# FullPrototypingBoard.net
KiCad netlist of a schematic drawn in EAGLE
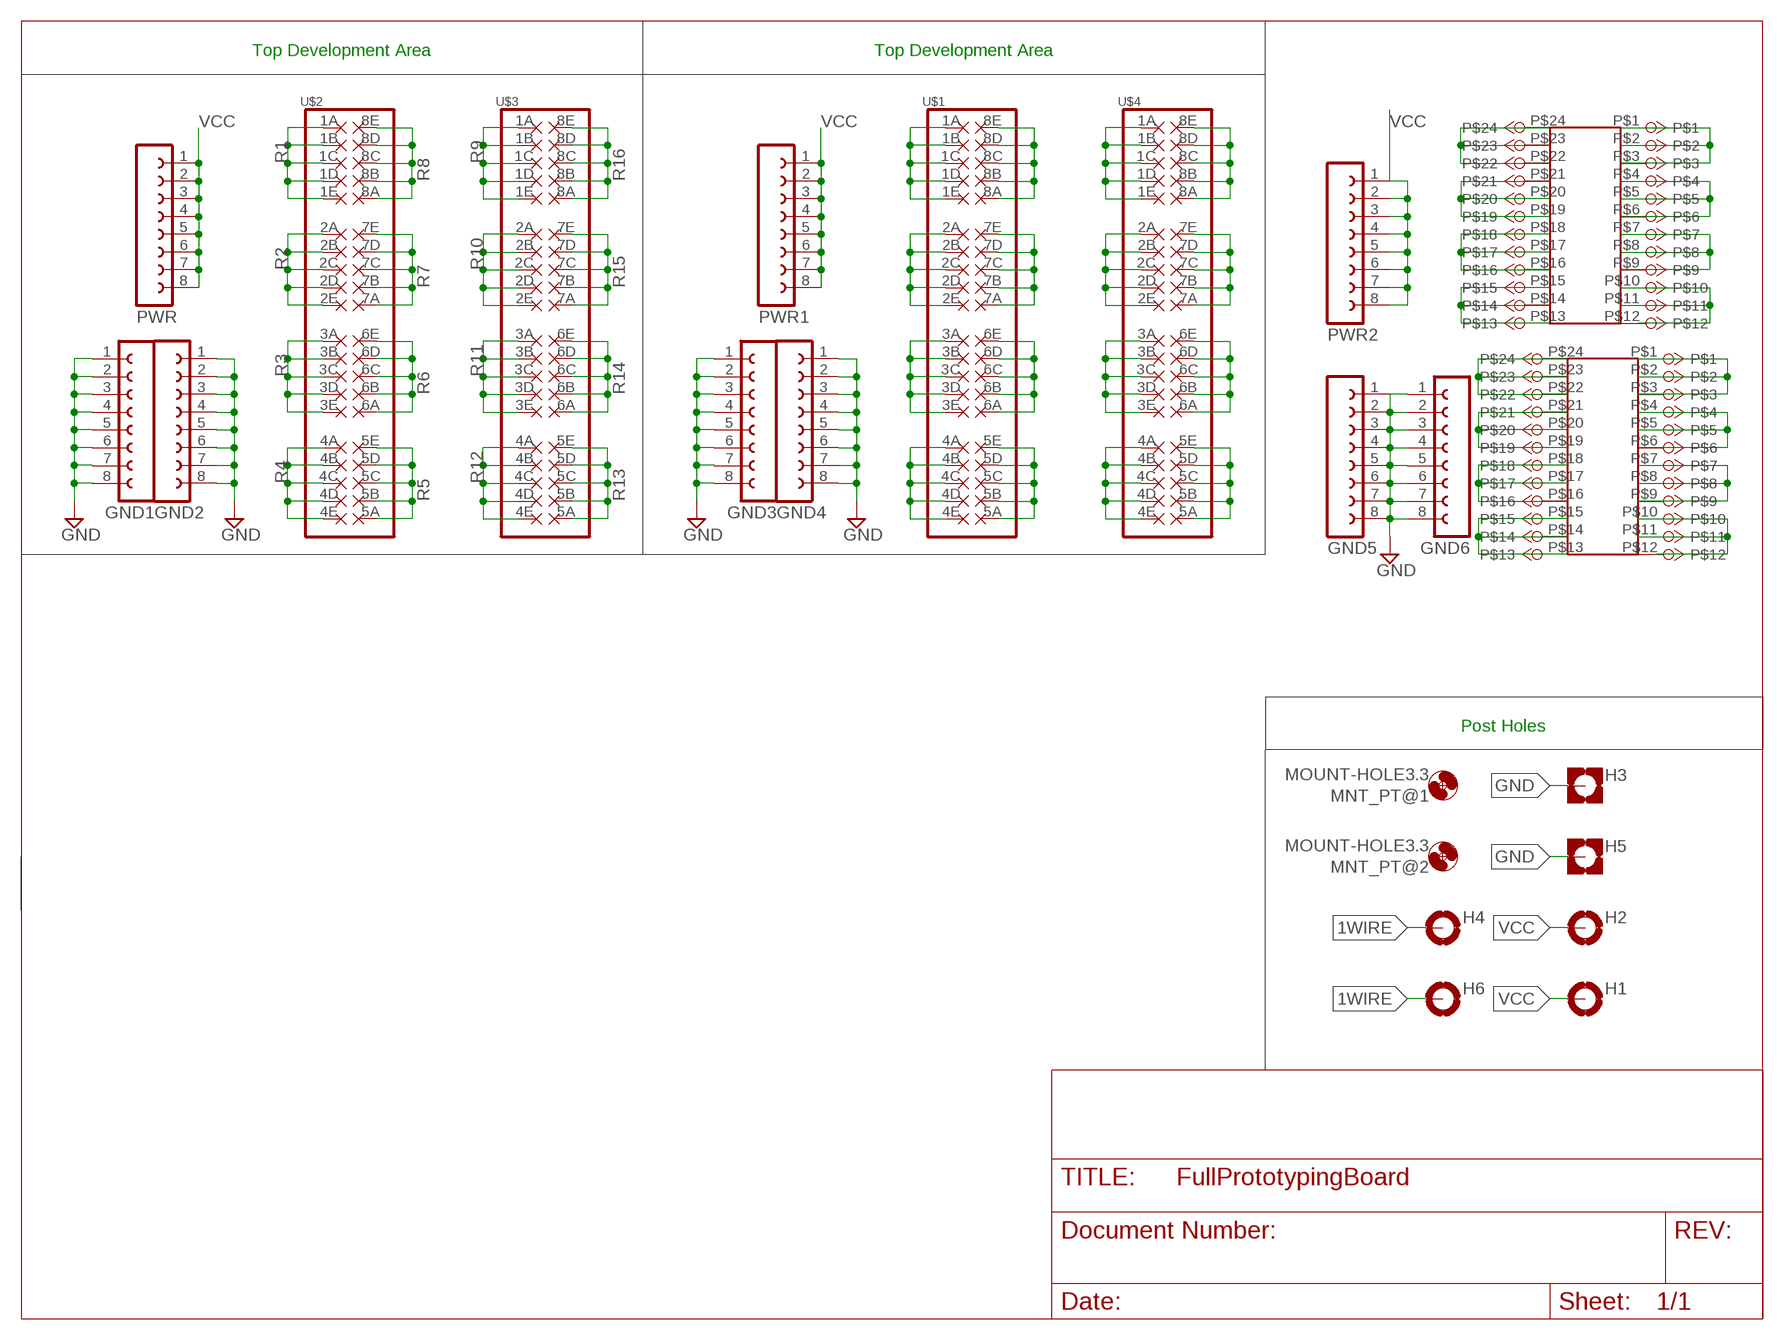
[diagram p0: schematic, sheet 1]

(export (version "E")
  (design (tool "Eeschema 10.0.6"))
  (components
    (comp (ref "GND1")
      (value "FE08-1-GND")
      (footprint "eagle-import:FE08-GND")
      (libsource (lib "eagle-import") (part "FE08-1-GND"))
    )
    (comp (ref "GND2")
      (value "FE08-1-GND")
      (footprint "eagle-import:FE08-GND")
      (libsource (lib "eagle-import") (part "FE08-1-GND"))
    )
    (comp (ref "GND3")
      (value "FE08-1-GND")
      (footprint "eagle-import:FE08-GND")
      (libsource (lib "eagle-import") (part "FE08-1-GND"))
    )
    (comp (ref "GND4")
      (value "FE08-1-GND")
      (footprint "eagle-import:FE08-GND")
      (libsource (lib "eagle-import") (part "FE08-1-GND"))
    )
    (comp (ref "GND5")
      (value "FE08-1-GND")
      (footprint "eagle-import:FE08-GND")
      (libsource (lib "eagle-import") (part "FE08-1-GND"))
    )
    (comp (ref "GND6")
      (value "FE08-1-GND")
      (footprint "eagle-import:FE08-GND")
      (libsource (lib "eagle-import") (part "FE08-1-GND"))
    )
    (comp (ref "H1")
      (value "MOUNT-PAD-ROUND3.3")
      (footprint "eagle-import:3,3-PAD")
      (libsource (lib "eagle-import") (part "MOUNT-PAD-ROUND3.3"))
    )
    (comp (ref "H2")
      (value "MOUNT-PAD-ROUND3.3")
      (footprint "eagle-import:3,3-PAD")
      (libsource (lib "eagle-import") (part "MOUNT-PAD-ROUND3.3"))
    )
    (comp (ref "H3")
      (value "MOUNT-PAD-SQUARE3.3")
      (footprint "eagle-import:3,3-PAD-SQUARE")
      (libsource (lib "eagle-import") (part "MOUNT-PAD-SQUARE3.3"))
    )
    (comp (ref "H4")
      (value "MOUNT-PAD-ROUND3.3")
      (footprint "eagle-import:3,3-PAD")
      (libsource (lib "eagle-import") (part "MOUNT-PAD-ROUND3.3"))
    )
    (comp (ref "H5")
      (value "MOUNT-PAD-SQUARE3.3")
      (footprint "eagle-import:3,3-PAD-SQUARE")
      (libsource (lib "eagle-import") (part "MOUNT-PAD-SQUARE3.3"))
    )
    (comp (ref "H6")
      (value "MOUNT-PAD-ROUND3.3")
      (footprint "eagle-import:3,3-PAD")
      (libsource (lib "eagle-import") (part "MOUNT-PAD-ROUND3.3"))
    )
    (comp (ref "MNT_PT@1")
      (value "MOUNT-HOLE3.3")
      (footprint "eagle-import:3,3")
      (libsource (lib "eagle-import") (part "MOUNT-HOLE3.3"))
    )
    (comp (ref "MNT_PT@2")
      (value "MOUNT-HOLE3.3")
      (footprint "eagle-import:3,3")
      (libsource (lib "eagle-import") (part "MOUNT-HOLE3.3"))
    )
    (comp (ref "PWR")
      (value "FE08-1")
      (footprint "eagle-import:FE08")
      (libsource (lib "eagle-import") (part "FE08-1"))
    )
    (comp (ref "PWR1")
      (value "FE08-1")
      (footprint "eagle-import:FE08")
      (libsource (lib "eagle-import") (part "FE08-1"))
    )
    (comp (ref "PWR2")
      (value "FE08-1")
      (footprint "eagle-import:FE08")
      (libsource (lib "eagle-import") (part "FE08-1"))
    )
    (comp (ref "U$1")
      (value "PROTO-5X8")
      (footprint "eagle-import:PROTO-5X08")
      (libsource (lib "eagle-import") (part "PROTO-5X8"))
    )
    (comp (ref "U$2")
      (value "PROTO-5X8")
      (footprint "eagle-import:PROTO-5X08")
      (libsource (lib "eagle-import") (part "PROTO-5X8"))
    )
    (comp (ref "U$3")
      (value "PROTO-5X8")
      (footprint "eagle-import:PROTO-5X08")
      (libsource (lib "eagle-import") (part "PROTO-5X8"))
    )
    (comp (ref "U$4")
      (value "PROTO-5X8")
      (footprint "eagle-import:PROTO-5X08")
      (libsource (lib "eagle-import") (part "PROTO-5X8"))
    )
    (comp (ref "U$5")
      (value "PROTO-3X8")
      (footprint "eagle-import:PROTO-3X08")
      (libsource (lib "eagle-import") (part "PROTO-3X8"))
    )
    (comp (ref "U$6")
      (value "PROTO-3X8")
      (footprint "eagle-import:PROTO-3X08")
      (libsource (lib "eagle-import") (part "PROTO-3X8"))
    )
  )
  (nets
    (net (code "1") (name "/R1") (class "Default")
      (node (ref "U$2") (pin "1A") (pinfunction "1A_1A") (pintype "passive"))
      (node (ref "U$2") (pin "1B") (pinfunction "1B_1B") (pintype "passive"))
      (node (ref "U$2") (pin "1C") (pinfunction "1C_1C") (pintype "passive"))
      (node (ref "U$2") (pin "1D") (pinfunction "1D_1D") (pintype "passive"))
      (node (ref "U$2") (pin "1E") (pinfunction "1E_1E") (pintype "passive"))
    )
    (net (code "2") (name "/R2") (class "Default")
      (node (ref "U$2") (pin "2A") (pinfunction "2A_2A") (pintype "passive"))
      (node (ref "U$2") (pin "2B") (pinfunction "2B_2B") (pintype "passive"))
      (node (ref "U$2") (pin "2C") (pinfunction "2C_2C") (pintype "passive"))
      (node (ref "U$2") (pin "2D") (pinfunction "2D_2D") (pintype "passive"))
      (node (ref "U$2") (pin "2E") (pinfunction "2E_2E") (pintype "passive"))
    )
    (net (code "3") (name "/R3") (class "Default")
      (node (ref "U$2") (pin "3A") (pinfunction "3A_3A") (pintype "passive"))
      (node (ref "U$2") (pin "3B") (pinfunction "3B_3B") (pintype "passive"))
      (node (ref "U$2") (pin "3C") (pinfunction "3C_3C") (pintype "passive"))
      (node (ref "U$2") (pin "3D") (pinfunction "3D_3D") (pintype "passive"))
      (node (ref "U$2") (pin "3E") (pinfunction "3E_3E") (pintype "passive"))
    )
    (net (code "4") (name "/R4") (class "Default")
      (node (ref "U$2") (pin "4A") (pinfunction "4A_4A") (pintype "passive"))
      (node (ref "U$2") (pin "4B") (pinfunction "4B_4B") (pintype "passive"))
      (node (ref "U$2") (pin "4C") (pinfunction "4C_4C") (pintype "passive"))
      (node (ref "U$2") (pin "4D") (pinfunction "4D_4D") (pintype "passive"))
      (node (ref "U$2") (pin "4E") (pinfunction "4E_4E") (pintype "passive"))
    )
    (net (code "5") (name "/R5") (class "Default")
      (node (ref "U$2") (pin "5A") (pinfunction "5A_5A") (pintype "passive"))
      (node (ref "U$2") (pin "5B") (pinfunction "5B_5B") (pintype "passive"))
      (node (ref "U$2") (pin "5C") (pinfunction "5C_5C") (pintype "passive"))
      (node (ref "U$2") (pin "5D") (pinfunction "5D_5D") (pintype "passive"))
      (node (ref "U$2") (pin "5E") (pinfunction "5E_5E") (pintype "passive"))
    )
    (net (code "6") (name "/R6") (class "Default")
      (node (ref "U$2") (pin "6A") (pinfunction "6A_6A") (pintype "passive"))
      (node (ref "U$2") (pin "6B") (pinfunction "6B_6B") (pintype "passive"))
      (node (ref "U$2") (pin "6C") (pinfunction "6C_6C") (pintype "passive"))
      (node (ref "U$2") (pin "6D") (pinfunction "6D_6D") (pintype "passive"))
      (node (ref "U$2") (pin "6E") (pinfunction "6E_6E") (pintype "passive"))
    )
    (net (code "7") (name "/R7") (class "Default")
      (node (ref "U$2") (pin "7A") (pinfunction "7A_7A") (pintype "passive"))
      (node (ref "U$2") (pin "7B") (pinfunction "7B_7B") (pintype "passive"))
      (node (ref "U$2") (pin "7C") (pinfunction "7C_7C") (pintype "passive"))
      (node (ref "U$2") (pin "7D") (pinfunction "7D_7D") (pintype "passive"))
      (node (ref "U$2") (pin "7E") (pinfunction "7E_7E") (pintype "passive"))
    )
    (net (code "8") (name "/R8") (class "Default")
      (node (ref "U$2") (pin "8A") (pinfunction "8A_8A") (pintype "passive"))
      (node (ref "U$2") (pin "8B") (pinfunction "8B_8B") (pintype "passive"))
      (node (ref "U$2") (pin "8C") (pinfunction "8C_8C") (pintype "passive"))
      (node (ref "U$2") (pin "8D") (pinfunction "8D_8D") (pintype "passive"))
      (node (ref "U$2") (pin "8E") (pinfunction "8E_8E") (pintype "passive"))
    )
    (net (code "9") (name "/R9") (class "Default")
      (node (ref "U$3") (pin "1A") (pinfunction "1A_1A") (pintype "passive"))
      (node (ref "U$3") (pin "1B") (pinfunction "1B_1B") (pintype "passive"))
      (node (ref "U$3") (pin "1C") (pinfunction "1C_1C") (pintype "passive"))
      (node (ref "U$3") (pin "1D") (pinfunction "1D_1D") (pintype "passive"))
      (node (ref "U$3") (pin "1E") (pinfunction "1E_1E") (pintype "passive"))
    )
    (net (code "10") (name "/R10") (class "Default")
      (node (ref "U$3") (pin "2A") (pinfunction "2A_2A") (pintype "passive"))
      (node (ref "U$3") (pin "2B") (pinfunction "2B_2B") (pintype "passive"))
      (node (ref "U$3") (pin "2C") (pinfunction "2C_2C") (pintype "passive"))
      (node (ref "U$3") (pin "2D") (pinfunction "2D_2D") (pintype "passive"))
      (node (ref "U$3") (pin "2E") (pinfunction "2E_2E") (pintype "passive"))
    )
    (net (code "11") (name "/R11") (class "Default")
      (node (ref "U$3") (pin "3A") (pinfunction "3A_3A") (pintype "passive"))
      (node (ref "U$3") (pin "3B") (pinfunction "3B_3B") (pintype "passive"))
      (node (ref "U$3") (pin "3C") (pinfunction "3C_3C") (pintype "passive"))
      (node (ref "U$3") (pin "3D") (pinfunction "3D_3D") (pintype "passive"))
      (node (ref "U$3") (pin "3E") (pinfunction "3E_3E") (pintype "passive"))
    )
    (net (code "12") (name "/R12") (class "Default")
      (node (ref "U$3") (pin "4A") (pinfunction "4A_4A") (pintype "passive"))
      (node (ref "U$3") (pin "4B") (pinfunction "4B_4B") (pintype "passive"))
      (node (ref "U$3") (pin "4C") (pinfunction "4C_4C") (pintype "passive"))
      (node (ref "U$3") (pin "4D") (pinfunction "4D_4D") (pintype "passive"))
      (node (ref "U$3") (pin "4E") (pinfunction "4E_4E") (pintype "passive"))
    )
    (net (code "13") (name "/R13") (class "Default")
      (node (ref "U$3") (pin "5A") (pinfunction "5A_5A") (pintype "passive"))
      (node (ref "U$3") (pin "5B") (pinfunction "5B_5B") (pintype "passive"))
      (node (ref "U$3") (pin "5C") (pinfunction "5C_5C") (pintype "passive"))
      (node (ref "U$3") (pin "5D") (pinfunction "5D_5D") (pintype "passive"))
      (node (ref "U$3") (pin "5E") (pinfunction "5E_5E") (pintype "passive"))
    )
    (net (code "14") (name "/R14") (class "Default")
      (node (ref "U$3") (pin "6A") (pinfunction "6A_6A") (pintype "passive"))
      (node (ref "U$3") (pin "6B") (pinfunction "6B_6B") (pintype "passive"))
      (node (ref "U$3") (pin "6C") (pinfunction "6C_6C") (pintype "passive"))
      (node (ref "U$3") (pin "6D") (pinfunction "6D_6D") (pintype "passive"))
      (node (ref "U$3") (pin "6E") (pinfunction "6E_6E") (pintype "passive"))
    )
    (net (code "15") (name "/R15") (class "Default")
      (node (ref "U$3") (pin "7A") (pinfunction "7A_7A") (pintype "passive"))
      (node (ref "U$3") (pin "7B") (pinfunction "7B_7B") (pintype "passive"))
      (node (ref "U$3") (pin "7C") (pinfunction "7C_7C") (pintype "passive"))
      (node (ref "U$3") (pin "7D") (pinfunction "7D_7D") (pintype "passive"))
      (node (ref "U$3") (pin "7E") (pinfunction "7E_7E") (pintype "passive"))
    )
    (net (code "16") (name "/R16") (class "Default")
      (node (ref "U$3") (pin "8A") (pinfunction "8A_8A") (pintype "passive"))
      (node (ref "U$3") (pin "8B") (pinfunction "8B_8B") (pintype "passive"))
      (node (ref "U$3") (pin "8C") (pinfunction "8C_8C") (pintype "passive"))
      (node (ref "U$3") (pin "8D") (pinfunction "8D_8D") (pintype "passive"))
      (node (ref "U$3") (pin "8E") (pinfunction "8E_8E") (pintype "passive"))
    )
    (net (code "17") (name "1WIRE") (class "Default")
      (node (ref "H4") (pin "B3,3") (pinfunction "MOUNT_B3,3") (pintype "passive"))
      (node (ref "H6") (pin "B3,3") (pinfunction "MOUNT_B3,3") (pintype "passive"))
    )
    (net (code "18") (name "GND") (class "Default")
      (node (ref "GND1") (pin "1") (pinfunction "1_1") (pintype "passive"))
      (node (ref "GND1") (pin "2") (pinfunction "2_2") (pintype "passive"))
      (node (ref "GND1") (pin "3") (pinfunction "3_3") (pintype "passive"))
      (node (ref "GND1") (pin "4") (pinfunction "4_4") (pintype "passive"))
      (node (ref "GND1") (pin "5") (pinfunction "5_5") (pintype "passive"))
      (node (ref "GND1") (pin "6") (pinfunction "6_6") (pintype "passive"))
      (node (ref "GND1") (pin "7") (pinfunction "7_7") (pintype "passive"))
      (node (ref "GND1") (pin "8") (pinfunction "8_8") (pintype "passive"))
      (node (ref "GND2") (pin "1") (pinfunction "1_1") (pintype "passive"))
      (node (ref "GND2") (pin "2") (pinfunction "2_2") (pintype "passive"))
      (node (ref "GND2") (pin "3") (pinfunction "3_3") (pintype "passive"))
      (node (ref "GND2") (pin "4") (pinfunction "4_4") (pintype "passive"))
      (node (ref "GND2") (pin "5") (pinfunction "5_5") (pintype "passive"))
      (node (ref "GND2") (pin "6") (pinfunction "6_6") (pintype "passive"))
      (node (ref "GND2") (pin "7") (pinfunction "7_7") (pintype "passive"))
      (node (ref "GND2") (pin "8") (pinfunction "8_8") (pintype "passive"))
      (node (ref "GND3") (pin "1") (pinfunction "1_1") (pintype "passive"))
      (node (ref "GND3") (pin "2") (pinfunction "2_2") (pintype "passive"))
      (node (ref "GND3") (pin "3") (pinfunction "3_3") (pintype "passive"))
      (node (ref "GND3") (pin "4") (pinfunction "4_4") (pintype "passive"))
      (node (ref "GND3") (pin "5") (pinfunction "5_5") (pintype "passive"))
      (node (ref "GND3") (pin "6") (pinfunction "6_6") (pintype "passive"))
      (node (ref "GND3") (pin "7") (pinfunction "7_7") (pintype "passive"))
      (node (ref "GND3") (pin "8") (pinfunction "8_8") (pintype "passive"))
      (node (ref "GND4") (pin "1") (pinfunction "1_1") (pintype "passive"))
      (node (ref "GND4") (pin "2") (pinfunction "2_2") (pintype "passive"))
      (node (ref "GND4") (pin "3") (pinfunction "3_3") (pintype "passive"))
      (node (ref "GND4") (pin "4") (pinfunction "4_4") (pintype "passive"))
      (node (ref "GND4") (pin "5") (pinfunction "5_5") (pintype "passive"))
      (node (ref "GND4") (pin "6") (pinfunction "6_6") (pintype "passive"))
      (node (ref "GND4") (pin "7") (pinfunction "7_7") (pintype "passive"))
      (node (ref "GND4") (pin "8") (pinfunction "8_8") (pintype "passive"))
      (node (ref "GND5") (pin "1") (pinfunction "1_1") (pintype "passive"))
      (node (ref "GND5") (pin "2") (pinfunction "2_2") (pintype "passive"))
      (node (ref "GND5") (pin "3") (pinfunction "3_3") (pintype "passive"))
      (node (ref "GND5") (pin "4") (pinfunction "4_4") (pintype "passive"))
      (node (ref "GND5") (pin "5") (pinfunction "5_5") (pintype "passive"))
      (node (ref "GND5") (pin "6") (pinfunction "6_6") (pintype "passive"))
      (node (ref "GND5") (pin "7") (pinfunction "7_7") (pintype "passive"))
      (node (ref "GND5") (pin "8") (pinfunction "8_8") (pintype "passive"))
      (node (ref "GND6") (pin "1") (pinfunction "1_1") (pintype "passive"))
      (node (ref "GND6") (pin "2") (pinfunction "2_2") (pintype "passive"))
      (node (ref "GND6") (pin "3") (pinfunction "3_3") (pintype "passive"))
      (node (ref "GND6") (pin "4") (pinfunction "4_4") (pintype "passive"))
      (node (ref "GND6") (pin "5") (pinfunction "5_5") (pintype "passive"))
      (node (ref "GND6") (pin "6") (pinfunction "6_6") (pintype "passive"))
      (node (ref "GND6") (pin "7") (pinfunction "7_7") (pintype "passive"))
      (node (ref "GND6") (pin "8") (pinfunction "8_8") (pintype "passive"))
      (node (ref "H3") (pin "B3,3") (pinfunction "MOUNT_B3,3") (pintype "passive"))
      (node (ref "H5") (pin "B3,3") (pinfunction "MOUNT_B3,3") (pintype "passive"))
    )
    (net (code "19") (name "Net-(U$1-Pad1A)") (class "Default")
      (node (ref "U$1") (pin "1A") (pinfunction "1A_1A") (pintype "passive"))
      (node (ref "U$1") (pin "1B") (pinfunction "1B_1B") (pintype "passive"))
      (node (ref "U$1") (pin "1C") (pinfunction "1C_1C") (pintype "passive"))
      (node (ref "U$1") (pin "1D") (pinfunction "1D_1D") (pintype "passive"))
      (node (ref "U$1") (pin "1E") (pinfunction "1E_1E") (pintype "passive"))
    )
    (net (code "20") (name "Net-(U$1-Pad2A)") (class "Default")
      (node (ref "U$1") (pin "2A") (pinfunction "2A_2A") (pintype "passive"))
      (node (ref "U$1") (pin "2B") (pinfunction "2B_2B") (pintype "passive"))
      (node (ref "U$1") (pin "2C") (pinfunction "2C_2C") (pintype "passive"))
      (node (ref "U$1") (pin "2D") (pinfunction "2D_2D") (pintype "passive"))
      (node (ref "U$1") (pin "2E") (pinfunction "2E_2E") (pintype "passive"))
    )
    (net (code "21") (name "Net-(U$1-Pad3A)") (class "Default")
      (node (ref "U$1") (pin "3A") (pinfunction "3A_3A") (pintype "passive"))
      (node (ref "U$1") (pin "3B") (pinfunction "3B_3B") (pintype "passive"))
      (node (ref "U$1") (pin "3C") (pinfunction "3C_3C") (pintype "passive"))
      (node (ref "U$1") (pin "3D") (pinfunction "3D_3D") (pintype "passive"))
      (node (ref "U$1") (pin "3E") (pinfunction "3E_3E") (pintype "passive"))
    )
    (net (code "22") (name "Net-(U$1-Pad4A)") (class "Default")
      (node (ref "U$1") (pin "4A") (pinfunction "4A_4A") (pintype "passive"))
      (node (ref "U$1") (pin "4B") (pinfunction "4B_4B") (pintype "passive"))
      (node (ref "U$1") (pin "4C") (pinfunction "4C_4C") (pintype "passive"))
      (node (ref "U$1") (pin "4D") (pinfunction "4D_4D") (pintype "passive"))
      (node (ref "U$1") (pin "4E") (pinfunction "4E_4E") (pintype "passive"))
    )
    (net (code "23") (name "Net-(U$1-Pad5A)") (class "Default")
      (node (ref "U$1") (pin "5A") (pinfunction "5A_5A") (pintype "passive"))
      (node (ref "U$1") (pin "5B") (pinfunction "5B_5B") (pintype "passive"))
      (node (ref "U$1") (pin "5C") (pinfunction "5C_5C") (pintype "passive"))
      (node (ref "U$1") (pin "5D") (pinfunction "5D_5D") (pintype "passive"))
      (node (ref "U$1") (pin "5E") (pinfunction "5E_5E") (pintype "passive"))
    )
    (net (code "24") (name "Net-(U$1-Pad6A)") (class "Default")
      (node (ref "U$1") (pin "6A") (pinfunction "6A_6A") (pintype "passive"))
      (node (ref "U$1") (pin "6B") (pinfunction "6B_6B") (pintype "passive"))
      (node (ref "U$1") (pin "6C") (pinfunction "6C_6C") (pintype "passive"))
      (node (ref "U$1") (pin "6D") (pinfunction "6D_6D") (pintype "passive"))
      (node (ref "U$1") (pin "6E") (pinfunction "6E_6E") (pintype "passive"))
    )
    (net (code "25") (name "Net-(U$1-Pad7A)") (class "Default")
      (node (ref "U$1") (pin "7A") (pinfunction "7A_7A") (pintype "passive"))
      (node (ref "U$1") (pin "7B") (pinfunction "7B_7B") (pintype "passive"))
      (node (ref "U$1") (pin "7C") (pinfunction "7C_7C") (pintype "passive"))
      (node (ref "U$1") (pin "7D") (pinfunction "7D_7D") (pintype "passive"))
      (node (ref "U$1") (pin "7E") (pinfunction "7E_7E") (pintype "passive"))
    )
    (net (code "26") (name "Net-(U$1-Pad8A)") (class "Default")
      (node (ref "U$1") (pin "8A") (pinfunction "8A_8A") (pintype "passive"))
      (node (ref "U$1") (pin "8B") (pinfunction "8B_8B") (pintype "passive"))
      (node (ref "U$1") (pin "8C") (pinfunction "8C_8C") (pintype "passive"))
      (node (ref "U$1") (pin "8D") (pinfunction "8D_8D") (pintype "passive"))
      (node (ref "U$1") (pin "8E") (pinfunction "8E_8E") (pintype "passive"))
    )
    (net (code "27") (name "Net-(U$4-Pad1A)") (class "Default")
      (node (ref "U$4") (pin "1A") (pinfunction "1A_1A") (pintype "passive"))
      (node (ref "U$4") (pin "1B") (pinfunction "1B_1B") (pintype "passive"))
      (node (ref "U$4") (pin "1C") (pinfunction "1C_1C") (pintype "passive"))
      (node (ref "U$4") (pin "1D") (pinfunction "1D_1D") (pintype "passive"))
      (node (ref "U$4") (pin "1E") (pinfunction "1E_1E") (pintype "passive"))
    )
    (net (code "28") (name "Net-(U$4-Pad2A)") (class "Default")
      (node (ref "U$4") (pin "2A") (pinfunction "2A_2A") (pintype "passive"))
      (node (ref "U$4") (pin "2B") (pinfunction "2B_2B") (pintype "passive"))
      (node (ref "U$4") (pin "2C") (pinfunction "2C_2C") (pintype "passive"))
      (node (ref "U$4") (pin "2D") (pinfunction "2D_2D") (pintype "passive"))
      (node (ref "U$4") (pin "2E") (pinfunction "2E_2E") (pintype "passive"))
    )
    (net (code "29") (name "Net-(U$4-Pad3A)") (class "Default")
      (node (ref "U$4") (pin "3A") (pinfunction "3A_3A") (pintype "passive"))
      (node (ref "U$4") (pin "3B") (pinfunction "3B_3B") (pintype "passive"))
      (node (ref "U$4") (pin "3C") (pinfunction "3C_3C") (pintype "passive"))
      (node (ref "U$4") (pin "3D") (pinfunction "3D_3D") (pintype "passive"))
      (node (ref "U$4") (pin "3E") (pinfunction "3E_3E") (pintype "passive"))
    )
    (net (code "30") (name "Net-(U$4-Pad4A)") (class "Default")
      (node (ref "U$4") (pin "4A") (pinfunction "4A_4A") (pintype "passive"))
      (node (ref "U$4") (pin "4B") (pinfunction "4B_4B") (pintype "passive"))
      (node (ref "U$4") (pin "4C") (pinfunction "4C_4C") (pintype "passive"))
      (node (ref "U$4") (pin "4D") (pinfunction "4D_4D") (pintype "passive"))
      (node (ref "U$4") (pin "4E") (pinfunction "4E_4E") (pintype "passive"))
    )
    (net (code "31") (name "Net-(U$4-Pad5A)") (class "Default")
      (node (ref "U$4") (pin "5A") (pinfunction "5A_5A") (pintype "passive"))
      (node (ref "U$4") (pin "5B") (pinfunction "5B_5B") (pintype "passive"))
      (node (ref "U$4") (pin "5C") (pinfunction "5C_5C") (pintype "passive"))
      (node (ref "U$4") (pin "5D") (pinfunction "5D_5D") (pintype "passive"))
      (node (ref "U$4") (pin "5E") (pinfunction "5E_5E") (pintype "passive"))
    )
    (net (code "32") (name "Net-(U$4-Pad6A)") (class "Default")
      (node (ref "U$4") (pin "6A") (pinfunction "6A_6A") (pintype "passive"))
      (node (ref "U$4") (pin "6B") (pinfunction "6B_6B") (pintype "passive"))
      (node (ref "U$4") (pin "6C") (pinfunction "6C_6C") (pintype "passive"))
      (node (ref "U$4") (pin "6D") (pinfunction "6D_6D") (pintype "passive"))
      (node (ref "U$4") (pin "6E") (pinfunction "6E_6E") (pintype "passive"))
    )
    (net (code "33") (name "Net-(U$4-Pad7A)") (class "Default")
      (node (ref "U$4") (pin "7A") (pinfunction "7A_7A") (pintype "passive"))
      (node (ref "U$4") (pin "7B") (pinfunction "7B_7B") (pintype "passive"))
      (node (ref "U$4") (pin "7C") (pinfunction "7C_7C") (pintype "passive"))
      (node (ref "U$4") (pin "7D") (pinfunction "7D_7D") (pintype "passive"))
      (node (ref "U$4") (pin "7E") (pinfunction "7E_7E") (pintype "passive"))
    )
    (net (code "34") (name "Net-(U$4-Pad8A)") (class "Default")
      (node (ref "U$4") (pin "8A") (pinfunction "8A_8A") (pintype "passive"))
      (node (ref "U$4") (pin "8B") (pinfunction "8B_8B") (pintype "passive"))
      (node (ref "U$4") (pin "8C") (pinfunction "8C_8C") (pintype "passive"))
      (node (ref "U$4") (pin "8D") (pinfunction "8D_8D") (pintype "passive"))
      (node (ref "U$4") (pin "8E") (pinfunction "8E_8E") (pintype "passive"))
    )
    (net (code "35") (name "Net-(U$5-PadP$1)") (class "Default")
      (node (ref "U$5") (pin "P$1") (pinfunction "P$1_P$1") (pintype "bidirectional"))
      (node (ref "U$5") (pin "P$2") (pinfunction "P$2_P$2") (pintype "bidirectional"))
      (node (ref "U$5") (pin "P$3") (pinfunction "P$3_P$3") (pintype "bidirectional"))
    )
    (net (code "36") (name "Net-(U$5-PadP$4)") (class "Default")
      (node (ref "U$5") (pin "P$4") (pinfunction "P$4_P$4") (pintype "bidirectional"))
      (node (ref "U$5") (pin "P$5") (pinfunction "P$5_P$5") (pintype "bidirectional"))
      (node (ref "U$5") (pin "P$6") (pinfunction "P$6_P$6") (pintype "bidirectional"))
    )
    (net (code "37") (name "Net-(U$5-PadP$7)") (class "Default")
      (node (ref "U$5") (pin "P$7") (pinfunction "P$7_P$7") (pintype "bidirectional"))
      (node (ref "U$5") (pin "P$8") (pinfunction "P$8_P$8") (pintype "bidirectional"))
      (node (ref "U$5") (pin "P$9") (pinfunction "P$9_P$9") (pintype "bidirectional"))
    )
    (net (code "38") (name "Net-(U$5-PadP$10)") (class "Default")
      (node (ref "U$5") (pin "P$10") (pinfunction "P$10_P$10") (pintype "bidirectional"))
      (node (ref "U$5") (pin "P$11") (pinfunction "P$11_P$11") (pintype "bidirectional"))
    )
    (net (code "39") (name "Net-(U$5-PadP$13)") (class "Default")
      (node (ref "U$5") (pin "P$13") (pinfunction "P$13_P$13") (pintype "bidirectional"))
      (node (ref "U$5") (pin "P$14") (pinfunction "P$14_P$14") (pintype "bidirectional"))
      (node (ref "U$5") (pin "P$15") (pinfunction "P$15_P$15") (pintype "bidirectional"))
    )
    (net (code "40") (name "Net-(U$5-PadP$16)") (class "Default")
      (node (ref "U$5") (pin "P$16") (pinfunction "P$16_P$16") (pintype "bidirectional"))
      (node (ref "U$5") (pin "P$17") (pinfunction "P$17_P$17") (pintype "bidirectional"))
      (node (ref "U$5") (pin "P$18") (pinfunction "P$18_P$18") (pintype "bidirectional"))
    )
    (net (code "41") (name "Net-(U$5-PadP$19)") (class "Default")
      (node (ref "U$5") (pin "P$19") (pinfunction "P$19_P$19") (pintype "bidirectional"))
      (node (ref "U$5") (pin "P$20") (pinfunction "P$20_P$20") (pintype "bidirectional"))
      (node (ref "U$5") (pin "P$21") (pinfunction "P$21_P$21") (pintype "bidirectional"))
    )
    (net (code "42") (name "Net-(U$5-PadP$22)") (class "Default")
      (node (ref "U$5") (pin "P$22") (pinfunction "P$22_P$22") (pintype "bidirectional"))
      (node (ref "U$5") (pin "P$23") (pinfunction "P$23_P$23") (pintype "bidirectional"))
      (node (ref "U$5") (pin "P$24") (pinfunction "P$24_P$24") (pintype "bidirectional"))
    )
    (net (code "43") (name "Net-(U$6-PadP$1)") (class "Default")
      (node (ref "U$6") (pin "P$1") (pinfunction "P$1_P$1") (pintype "bidirectional"))
      (node (ref "U$6") (pin "P$2") (pinfunction "P$2_P$2") (pintype "bidirectional"))
      (node (ref "U$6") (pin "P$3") (pinfunction "P$3_P$3") (pintype "bidirectional"))
    )
    (net (code "44") (name "Net-(U$6-PadP$4)") (class "Default")
      (node (ref "U$6") (pin "P$4") (pinfunction "P$4_P$4") (pintype "bidirectional"))
      (node (ref "U$6") (pin "P$5") (pinfunction "P$5_P$5") (pintype "bidirectional"))
      (node (ref "U$6") (pin "P$6") (pinfunction "P$6_P$6") (pintype "bidirectional"))
    )
    (net (code "45") (name "Net-(U$6-PadP$7)") (class "Default")
      (node (ref "U$6") (pin "P$7") (pinfunction "P$7_P$7") (pintype "bidirectional"))
      (node (ref "U$6") (pin "P$8") (pinfunction "P$8_P$8") (pintype "bidirectional"))
      (node (ref "U$6") (pin "P$9") (pinfunction "P$9_P$9") (pintype "bidirectional"))
    )
    (net (code "46") (name "Net-(U$6-PadP$10)") (class "Default")
      (node (ref "U$6") (pin "P$10") (pinfunction "P$10_P$10") (pintype "bidirectional"))
      (node (ref "U$6") (pin "P$11") (pinfunction "P$11_P$11") (pintype "bidirectional"))
    )
    (net (code "47") (name "Net-(U$6-PadP$13)") (class "Default")
      (node (ref "U$6") (pin "P$13") (pinfunction "P$13_P$13") (pintype "bidirectional"))
      (node (ref "U$6") (pin "P$14") (pinfunction "P$14_P$14") (pintype "bidirectional"))
      (node (ref "U$6") (pin "P$15") (pinfunction "P$15_P$15") (pintype "bidirectional"))
    )
    (net (code "48") (name "Net-(U$6-PadP$16)") (class "Default")
      (node (ref "U$6") (pin "P$16") (pinfunction "P$16_P$16") (pintype "bidirectional"))
      (node (ref "U$6") (pin "P$17") (pinfunction "P$17_P$17") (pintype "bidirectional"))
      (node (ref "U$6") (pin "P$18") (pinfunction "P$18_P$18") (pintype "bidirectional"))
    )
    (net (code "49") (name "Net-(U$6-PadP$19)") (class "Default")
      (node (ref "U$6") (pin "P$19") (pinfunction "P$19_P$19") (pintype "bidirectional"))
      (node (ref "U$6") (pin "P$20") (pinfunction "P$20_P$20") (pintype "bidirectional"))
      (node (ref "U$6") (pin "P$21") (pinfunction "P$21_P$21") (pintype "bidirectional"))
    )
    (net (code "50") (name "Net-(U$6-PadP$22)") (class "Default")
      (node (ref "U$6") (pin "P$22") (pinfunction "P$22_P$22") (pintype "bidirectional"))
      (node (ref "U$6") (pin "P$23") (pinfunction "P$23_P$23") (pintype "bidirectional"))
      (node (ref "U$6") (pin "P$24") (pinfunction "P$24_P$24") (pintype "bidirectional"))
    )
    (net (code "51") (name "VCC") (class "Default")
      (node (ref "H1") (pin "B3,3") (pinfunction "MOUNT_B3,3") (pintype "passive"))
      (node (ref "H2") (pin "B3,3") (pinfunction "MOUNT_B3,3") (pintype "passive"))
      (node (ref "PWR") (pin "1") (pinfunction "1_1") (pintype "passive"))
      (node (ref "PWR") (pin "2") (pinfunction "2_2") (pintype "passive"))
      (node (ref "PWR") (pin "3") (pinfunction "3_3") (pintype "passive"))
      (node (ref "PWR") (pin "4") (pinfunction "4_4") (pintype "passive"))
      (node (ref "PWR") (pin "5") (pinfunction "5_5") (pintype "passive"))
      (node (ref "PWR") (pin "6") (pinfunction "6_6") (pintype "passive"))
      (node (ref "PWR") (pin "7") (pinfunction "7_7") (pintype "passive"))
      (node (ref "PWR") (pin "8") (pinfunction "8_8") (pintype "passive"))
      (node (ref "PWR1") (pin "1") (pinfunction "1_1") (pintype "passive"))
      (node (ref "PWR1") (pin "2") (pinfunction "2_2") (pintype "passive"))
      (node (ref "PWR1") (pin "3") (pinfunction "3_3") (pintype "passive"))
      (node (ref "PWR1") (pin "4") (pinfunction "4_4") (pintype "passive"))
      (node (ref "PWR1") (pin "5") (pinfunction "5_5") (pintype "passive"))
      (node (ref "PWR1") (pin "6") (pinfunction "6_6") (pintype "passive"))
      (node (ref "PWR1") (pin "7") (pinfunction "7_7") (pintype "passive"))
      (node (ref "PWR1") (pin "8") (pinfunction "8_8") (pintype "passive"))
      (node (ref "PWR2") (pin "1") (pinfunction "1_1") (pintype "passive"))
      (node (ref "PWR2") (pin "2") (pinfunction "2_2") (pintype "passive"))
      (node (ref "PWR2") (pin "3") (pinfunction "3_3") (pintype "passive"))
      (node (ref "PWR2") (pin "4") (pinfunction "4_4") (pintype "passive"))
      (node (ref "PWR2") (pin "5") (pinfunction "5_5") (pintype "passive"))
      (node (ref "PWR2") (pin "6") (pinfunction "6_6") (pintype "passive"))
      (node (ref "PWR2") (pin "7") (pinfunction "7_7") (pintype "passive"))
      (node (ref "PWR2") (pin "8") (pinfunction "8_8") (pintype "passive"))
    )
    (net (code "52") (name "unconnected-(U$5-PadP$12)") (class "Default")
      (node (ref "U$5") (pin "P$12") (pinfunction "P$12_P$12") (pintype "bidirectional"))
    )
    (net (code "53") (name "unconnected-(U$6-PadP$12)") (class "Default")
      (node (ref "U$6") (pin "P$12") (pinfunction "P$12_P$12") (pintype "bidirectional"))
    )
  )
)
